# CTU.net
KiCad netlist of a schematic drawn in EAGLE
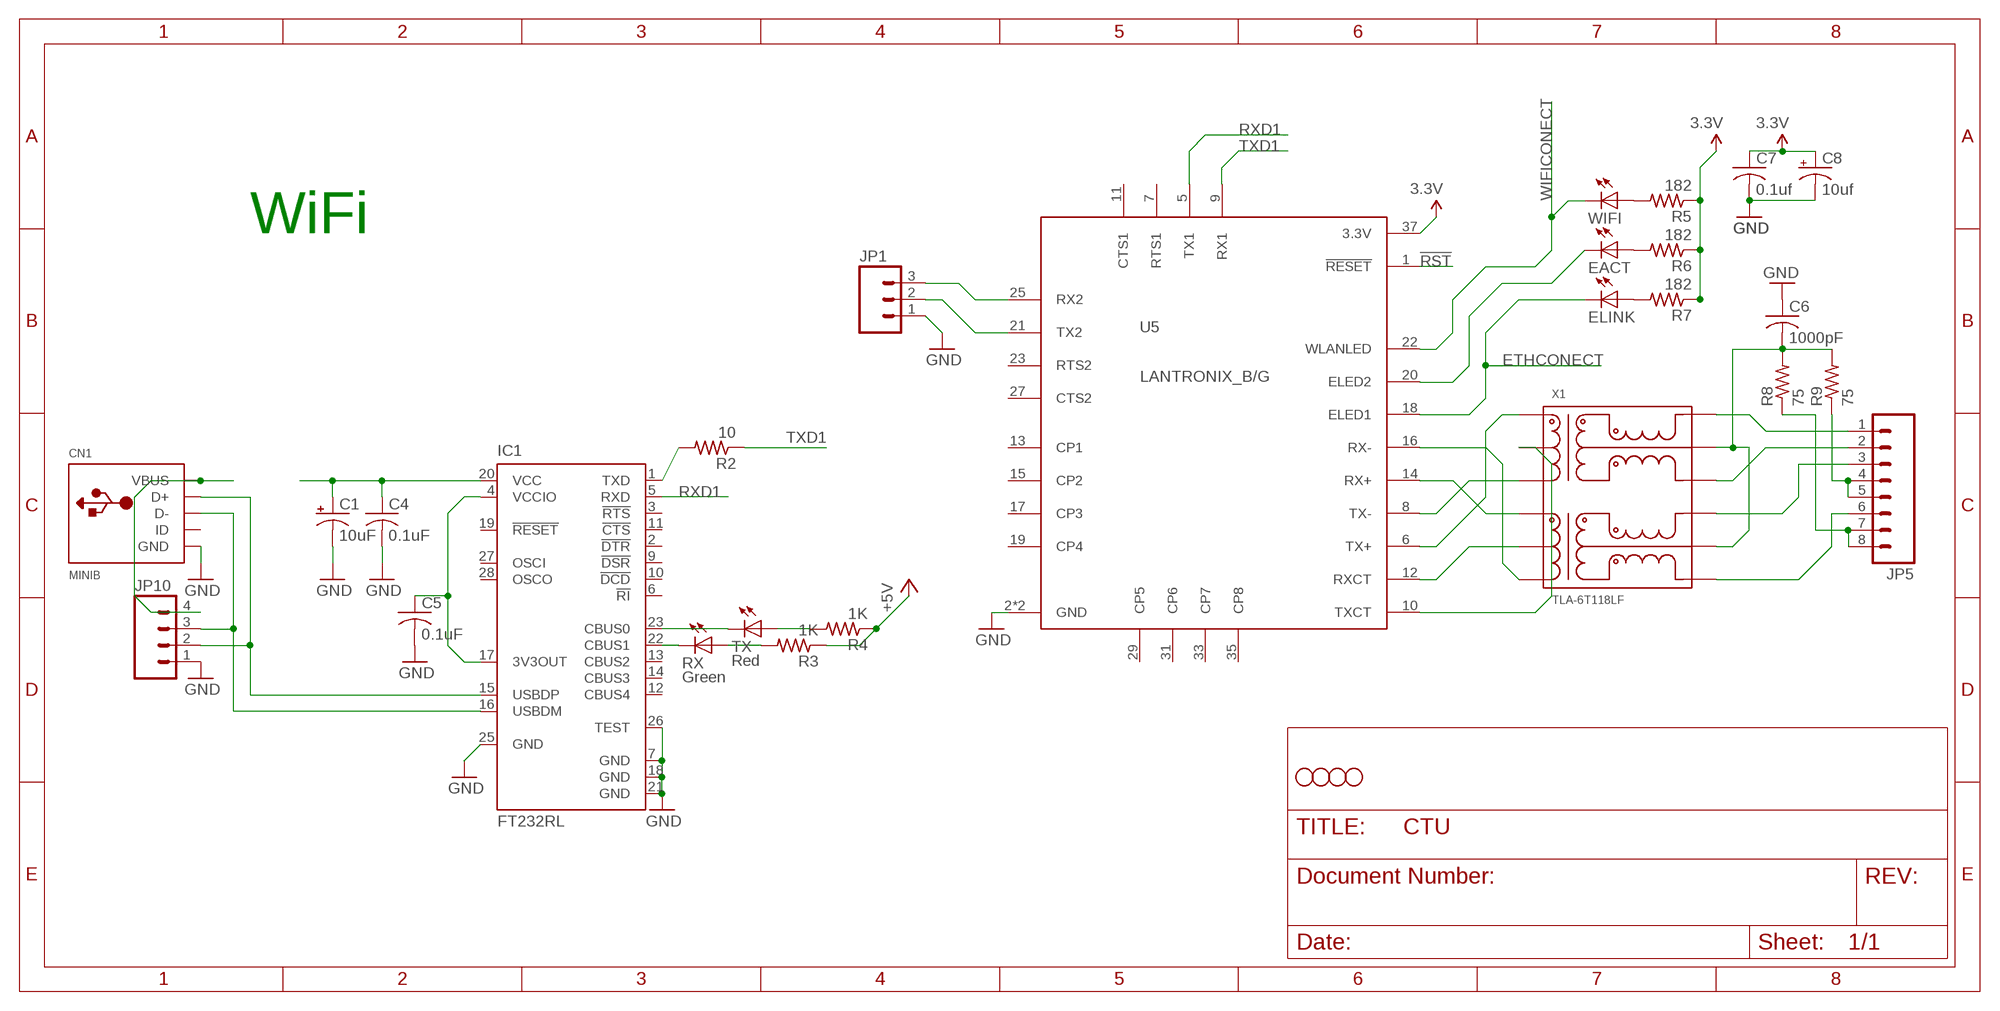
[diagram p0: schematic, sheet 1]

(export (version "E")
  (design (tool "Eeschema 10.0.6"))
  (components
    (comp (ref "C1")
      (value "10uF")
      (footprint "eagle-import:EIA3528-KIT")
      (libsource (lib "eagle-import") (part "CAP_POL3528-KIT"))
    )
    (comp (ref "C4")
      (value "0.1uF")
      (footprint "eagle-import:C0805K")
      (libsource (lib "eagle-import") (part "C-USC0805K"))
    )
    (comp (ref "C5")
      (value "0.1uF")
      (footprint "eagle-import:C0805K")
      (libsource (lib "eagle-import") (part "C-USC0805K"))
    )
    (comp (ref "C6")
      (value "1000pF")
      (footprint "eagle-import:C1812")
      (libsource (lib "eagle-import") (part "C-USC1812"))
    )
    (comp (ref "C7")
      (value "0.1uf")
      (footprint "eagle-import:C0805K")
      (libsource (lib "eagle-import") (part "C-USC0805K"))
    )
    (comp (ref "C8")
      (value "10uf")
      (footprint "eagle-import:EIA3528")
      (libsource (lib "eagle-import") (part "CAP_POL3528"))
    )
    (comp (ref "CN1")
      (value "MINIB")
      (footprint "eagle-import:USB-MINIB")
      (libsource (lib "eagle-import") (part "USBMINIB"))
    )
    (comp (ref "EACT")
      (value "LEDCHIP-LED0805")
      (footprint "eagle-import:CHIP-LED0805")
      (libsource (lib "eagle-import") (part "LEDCHIP-LED0805"))
    )
    (comp (ref "ELINK")
      (value "LEDCHIP-LED0805")
      (footprint "eagle-import:CHIP-LED0805")
      (libsource (lib "eagle-import") (part "LEDCHIP-LED0805"))
    )
    (comp (ref "IC1")
      (value "FT232RL")
      (footprint "eagle-import:SSOP28")
      (libsource (lib "eagle-import") (part "FT232RL"))
    )
    (comp (ref "JP1")
      (value "M03POLAR")
      (footprint "eagle-import:MOLEX-1X3")
      (libsource (lib "eagle-import") (part "M03POLAR"))
    )
    (comp (ref "JP2")
      (value "STAND-OFF")
      (footprint "eagle-import:STAND-OFF")
      (libsource (lib "eagle-import") (part "STAND-OFF"))
    )
    (comp (ref "JP3")
      (value "STAND-OFF")
      (footprint "eagle-import:STAND-OFF")
      (libsource (lib "eagle-import") (part "STAND-OFF"))
    )
    (comp (ref "JP4")
      (value "STAND-OFF")
      (footprint "eagle-import:STAND-OFF")
      (libsource (lib "eagle-import") (part "STAND-OFF"))
    )
    (comp (ref "JP5")
      (value "M08LOCK_LONGPADS")
      (footprint "eagle-import:1X08_LOCK_LONGPADS")
      (libsource (lib "eagle-import") (part "M08LOCK_LONGPADS"))
    )
    (comp (ref "JP6")
      (value "STAND-OFF")
      (footprint "eagle-import:STAND-OFF")
      (libsource (lib "eagle-import") (part "STAND-OFF"))
    )
    (comp (ref "JP10")
      (value "M04POLAR")
      (footprint "eagle-import:MOLEX-1X4")
      (libsource (lib "eagle-import") (part "M04POLAR"))
    )
    (comp (ref "R2")
      (value "10")
      (footprint "eagle-import:R0805")
      (libsource (lib "eagle-import") (part "R-US_R0805"))
    )
    (comp (ref "R3")
      (value "1K")
      (footprint "eagle-import:R0805")
      (libsource (lib "eagle-import") (part "R-US_R0805"))
    )
    (comp (ref "R4")
      (value "1K")
      (footprint "eagle-import:R0805")
      (libsource (lib "eagle-import") (part "R-US_R0805"))
    )
    (comp (ref "R5")
      (value "182")
      (footprint "eagle-import:R0805")
      (libsource (lib "eagle-import") (part "R-US_R0805"))
    )
    (comp (ref "R6")
      (value "182")
      (footprint "eagle-import:R0805")
      (libsource (lib "eagle-import") (part "R-US_R0805"))
    )
    (comp (ref "R7")
      (value "182")
      (footprint "eagle-import:R0805")
      (libsource (lib "eagle-import") (part "R-US_R0805"))
    )
    (comp (ref "R8")
      (value "75")
      (footprint "eagle-import:R0805")
      (libsource (lib "eagle-import") (part "R-US_R0805"))
    )
    (comp (ref "R9")
      (value "75")
      (footprint "eagle-import:R0805")
      (libsource (lib "eagle-import") (part "R-US_R0805"))
    )
    (comp (ref "RX")
      (value "Green")
      (footprint "eagle-import:CHIP-LED0805")
      (libsource (lib "eagle-import") (part "LEDCHIP-LED0805"))
    )
    (comp (ref "TX")
      (value "Red")
      (footprint "eagle-import:CHIP-LED0805")
      (libsource (lib "eagle-import") (part "LEDCHIP-LED0805"))
    )
    (comp (ref "U5")
      (value "LANTRONIX_B/G")
      (footprint "eagle-import:LANA_BTH")
      (libsource (lib "eagle-import") (part "LANTRONIX_A/B"))
    )
    (comp (ref "WIFI")
      (value "LEDCHIP-LED0805")
      (footprint "eagle-import:CHIP-LED0805")
      (libsource (lib "eagle-import") (part "LEDCHIP-LED0805"))
    )
    (comp (ref "X1")
      (value "TLA-6T118LF")
      (footprint "eagle-import:SO-16MOD")
      (libsource (lib "eagle-import") (part "TLA-6T118LF"))
    )
  )
  (nets
    (net (code "1") (name "+5V") (class "Default")
      (node (ref "R3") (pin "1") (pinfunction "1_1") (pintype "passive"))
      (node (ref "R4") (pin "1") (pinfunction "1_1") (pintype "passive"))
    )
    (net (code "2") (name "/ETHCONECT") (class "Default")
      (node (ref "ELINK") (pin "C") (pinfunction "C_C") (pintype "passive"))
      (node (ref "U5") (pin "18") (pinfunction "ELED1_18") (pintype "bidirectional"))
    )
    (net (code "3") (name "/RXD1") (class "Default")
      (node (ref "IC1") (pin "5") (pinfunction "RXD_5") (pintype "input"))
      (node (ref "U5") (pin "5") (pinfunction "TX1_5") (pintype "bidirectional"))
    )
    (net (code "4") (name "/TXD1") (class "Default")
      (node (ref "R2") (pin "1") (pinfunction "1_1") (pintype "passive"))
      (node (ref "U5") (pin "9") (pinfunction "RX1_9") (pintype "bidirectional"))
    )
    (net (code "5") (name "/WIFICONECT") (class "Default")
      (node (ref "U5") (pin "22") (pinfunction "WLANLED_22") (pintype "bidirectional"))
      (node (ref "WIFI") (pin "C") (pinfunction "C_C") (pintype "passive"))
    )
    (net (code "6") (name "/~{RST}") (class "Default")
      (node (ref "U5") (pin "1") (pinfunction "~{RESET}_1") (pintype "bidirectional"))
    )
    (net (code "7") (name "3.3V") (class "Default")
      (node (ref "C7") (pin "1") (pinfunction "1_1") (pintype "passive"))
      (node (ref "C8") (pin "A") (pinfunction "+_A") (pintype "passive"))
      (node (ref "R5") (pin "1") (pinfunction "1_1") (pintype "passive"))
      (node (ref "R6") (pin "1") (pinfunction "1_1") (pintype "passive"))
      (node (ref "R7") (pin "1") (pinfunction "1_1") (pintype "passive"))
      (node (ref "U5") (pin "37") (pinfunction "3.3V_37") (pintype "bidirectional"))
    )
    (net (code "8") (name "GND") (class "Default")
      (node (ref "C1") (pin "C") (pinfunction "-_C") (pintype "passive"))
      (node (ref "C4") (pin "2") (pinfunction "2_2") (pintype "passive"))
      (node (ref "C5") (pin "2") (pinfunction "2_2") (pintype "passive"))
      (node (ref "C6") (pin "1") (pinfunction "1_1") (pintype "passive"))
      (node (ref "C7") (pin "2") (pinfunction "2_2") (pintype "passive"))
      (node (ref "C8") (pin "C") (pinfunction "-_C") (pintype "passive"))
      (node (ref "CN1") (pin "GND") (pinfunction "GND_GND") (pintype "power_in"))
      (node (ref "IC1") (pin "18") (pinfunction "GND_18") (pintype "input"))
      (node (ref "IC1") (pin "21") (pinfunction "GND_21") (pintype "input"))
      (node (ref "IC1") (pin "25") (pinfunction "GND_25") (pintype "input"))
      (node (ref "IC1") (pin "26") (pinfunction "TEST_26") (pintype "input"))
      (node (ref "IC1") (pin "7") (pinfunction "GND_7") (pintype "input"))
      (node (ref "JP1") (pin "1") (pinfunction "1_1") (pintype "passive"))
      (node (ref "JP10") (pin "1") (pinfunction "1_1") (pintype "passive"))
      (node (ref "U5") (pin "2") (pinfunction "GND_2") (pintype "bidirectional"))
      (node (ref "U5") (pin "39") (pinfunction "GND_39") (pintype "bidirectional"))
    )
    (net (code "9") (name "Net-(C1-+)") (class "Default")
      (node (ref "C1") (pin "A") (pinfunction "+_A") (pintype "passive"))
      (node (ref "C4") (pin "1") (pinfunction "1_1") (pintype "passive"))
      (node (ref "IC1") (pin "20") (pinfunction "VCC_20") (pintype "input"))
    )
    (net (code "10") (name "Net-(C6-Pad2)") (class "Default")
      (node (ref "C6") (pin "2") (pinfunction "2_2") (pintype "passive"))
      (node (ref "R8") (pin "2") (pinfunction "2_2") (pintype "passive"))
      (node (ref "R9") (pin "2") (pinfunction "2_2") (pintype "passive"))
      (node (ref "X1") (pin "10") (pinfunction "10_10") (pintype "bidirectional"))
      (node (ref "X1") (pin "15") (pinfunction "15_15") (pintype "bidirectional"))
    )
    (net (code "11") (name "Net-(CN1-PadVBUS)") (class "Default")
      (node (ref "CN1") (pin "VBUS") (pinfunction "VBUS_VBUS") (pintype "power_in"))
      (node (ref "JP10") (pin "4") (pinfunction "4_4") (pintype "passive"))
    )
    (net (code "12") (name "Net-(EACT-PadA)") (class "Default")
      (node (ref "EACT") (pin "A") (pinfunction "A_A") (pintype "passive"))
      (node (ref "R6") (pin "2") (pinfunction "2_2") (pintype "passive"))
    )
    (net (code "13") (name "Net-(ELINK-PadA)") (class "Default")
      (node (ref "ELINK") (pin "A") (pinfunction "A_A") (pintype "passive"))
      (node (ref "R7") (pin "2") (pinfunction "2_2") (pintype "passive"))
    )
    (net (code "14") (name "Net-(IC1-3V3OUT)") (class "Default")
      (node (ref "C5") (pin "1") (pinfunction "1_1") (pintype "passive"))
      (node (ref "IC1") (pin "17") (pinfunction "3V3OUT_17") (pintype "input"))
      (node (ref "IC1") (pin "4") (pinfunction "VCCIO_4") (pintype "input"))
    )
    (net (code "15") (name "Net-(IC1-CBUS0)") (class "Default")
      (node (ref "IC1") (pin "23") (pinfunction "CBUS0_23") (pintype "input"))
      (node (ref "TX") (pin "C") (pinfunction "C_C") (pintype "passive"))
    )
    (net (code "16") (name "Net-(IC1-CBUS1)") (class "Default")
      (node (ref "IC1") (pin "22") (pinfunction "CBUS1_22") (pintype "input"))
      (node (ref "RX") (pin "C") (pinfunction "C_C") (pintype "passive"))
    )
    (net (code "17") (name "Net-(IC1-TXD)") (class "Default")
      (node (ref "IC1") (pin "1") (pinfunction "TXD_1") (pintype "input"))
      (node (ref "R2") (pin "2") (pinfunction "2_2") (pintype "passive"))
    )
    (net (code "18") (name "Net-(IC1-USBDM)") (class "Default")
      (node (ref "CN1") (pin "D-") (pinfunction "D-_D-") (pintype "bidirectional"))
      (node (ref "IC1") (pin "16") (pinfunction "USBDM_16") (pintype "input"))
      (node (ref "JP10") (pin "3") (pinfunction "3_3") (pintype "passive"))
    )
    (net (code "19") (name "Net-(IC1-USBDP)") (class "Default")
      (node (ref "CN1") (pin "D+") (pinfunction "D+_D+") (pintype "bidirectional"))
      (node (ref "IC1") (pin "15") (pinfunction "USBDP_15") (pintype "input"))
      (node (ref "JP10") (pin "2") (pinfunction "2_2") (pintype "passive"))
    )
    (net (code "20") (name "Net-(JP5-Pad1)") (class "Default")
      (node (ref "JP5") (pin "1") (pinfunction "1_1") (pintype "passive"))
      (node (ref "X1") (pin "16") (pinfunction "16_16") (pintype "bidirectional"))
    )
    (net (code "21") (name "Net-(JP5-Pad2)") (class "Default")
      (node (ref "JP5") (pin "2") (pinfunction "2_2") (pintype "passive"))
      (node (ref "X1") (pin "14") (pinfunction "14_14") (pintype "bidirectional"))
    )
    (net (code "22") (name "Net-(JP5-Pad3)") (class "Default")
      (node (ref "JP5") (pin "3") (pinfunction "3_3") (pintype "passive"))
      (node (ref "X1") (pin "11") (pinfunction "11_11") (pintype "bidirectional"))
    )
    (net (code "23") (name "Net-(JP5-Pad4)") (class "Default")
      (node (ref "JP5") (pin "4") (pinfunction "4_4") (pintype "passive"))
      (node (ref "JP5") (pin "5") (pinfunction "5_5") (pintype "passive"))
      (node (ref "R9") (pin "1") (pinfunction "1_1") (pintype "passive"))
    )
    (net (code "24") (name "Net-(JP5-Pad6)") (class "Default")
      (node (ref "JP5") (pin "6") (pinfunction "6_6") (pintype "passive"))
      (node (ref "X1") (pin "9") (pinfunction "9_9") (pintype "bidirectional"))
    )
    (net (code "25") (name "Net-(JP5-Pad7)") (class "Default")
      (node (ref "JP5") (pin "7") (pinfunction "7_7") (pintype "passive"))
      (node (ref "JP5") (pin "8") (pinfunction "8_8") (pintype "passive"))
      (node (ref "R8") (pin "1") (pinfunction "1_1") (pintype "passive"))
    )
    (net (code "26") (name "Net-(R3-Pad2)") (class "Default")
      (node (ref "R3") (pin "2") (pinfunction "2_2") (pintype "passive"))
      (node (ref "RX") (pin "A") (pinfunction "A_A") (pintype "passive"))
    )
    (net (code "27") (name "Net-(R4-Pad2)") (class "Default")
      (node (ref "R4") (pin "2") (pinfunction "2_2") (pintype "passive"))
      (node (ref "TX") (pin "A") (pinfunction "A_A") (pintype "passive"))
    )
    (net (code "28") (name "Net-(R5-Pad2)") (class "Default")
      (node (ref "R5") (pin "2") (pinfunction "2_2") (pintype "passive"))
      (node (ref "WIFI") (pin "A") (pinfunction "A_A") (pintype "passive"))
    )
    (net (code "29") (name "Net-(U5-ELED2)") (class "Default")
      (node (ref "EACT") (pin "C") (pinfunction "C_C") (pintype "passive"))
      (node (ref "U5") (pin "20") (pinfunction "ELED2_20") (pintype "bidirectional"))
    )
    (net (code "30") (name "Net-(U5-RX+)") (class "Default")
      (node (ref "U5") (pin "14") (pinfunction "RX+_14") (pintype "bidirectional"))
      (node (ref "X1") (pin "6") (pinfunction "6_6") (pintype "bidirectional"))
    )
    (net (code "31") (name "Net-(U5-RX-)") (class "Default")
      (node (ref "U5") (pin "16") (pinfunction "RX-_16") (pintype "bidirectional"))
      (node (ref "X1") (pin "8") (pinfunction "8_8") (pintype "bidirectional"))
    )
    (net (code "32") (name "Net-(U5-RX2)") (class "Default")
      (node (ref "JP1") (pin "3") (pinfunction "3_3") (pintype "passive"))
      (node (ref "U5") (pin "25") (pinfunction "RX2_25") (pintype "bidirectional"))
    )
    (net (code "33") (name "Net-(U5-RXCT)") (class "Default")
      (node (ref "U5") (pin "12") (pinfunction "RXCT_12") (pintype "bidirectional"))
      (node (ref "X1") (pin "7") (pinfunction "7_7") (pintype "bidirectional"))
    )
    (net (code "34") (name "Net-(U5-TX+)") (class "Default")
      (node (ref "U5") (pin "6") (pinfunction "TX+_6") (pintype "bidirectional"))
      (node (ref "X1") (pin "1") (pinfunction "1_1") (pintype "bidirectional"))
    )
    (net (code "35") (name "Net-(U5-TX-)") (class "Default")
      (node (ref "U5") (pin "8") (pinfunction "TX-_8") (pintype "bidirectional"))
      (node (ref "X1") (pin "3") (pinfunction "3_3") (pintype "bidirectional"))
    )
    (net (code "36") (name "Net-(U5-TX2)") (class "Default")
      (node (ref "JP1") (pin "2") (pinfunction "2_2") (pintype "passive"))
      (node (ref "U5") (pin "21") (pinfunction "TX2_21") (pintype "bidirectional"))
    )
    (net (code "37") (name "Net-(U5-TXCT)") (class "Default")
      (node (ref "U5") (pin "10") (pinfunction "TXCT_10") (pintype "bidirectional"))
      (node (ref "X1") (pin "2") (pinfunction "2_2") (pintype "bidirectional"))
    )
    (net (code "38") (name "unconnected-(CN1-PadID)") (class "Default")
      (node (ref "CN1") (pin "ID") (pinfunction "ID_ID") (pintype "bidirectional"))
    )
    (net (code "39") (name "unconnected-(IC1-CBUS2-Pad13)") (class "Default")
      (node (ref "IC1") (pin "13") (pinfunction "CBUS2_13") (pintype "input"))
    )
    (net (code "40") (name "unconnected-(IC1-CBUS3-Pad14)") (class "Default")
      (node (ref "IC1") (pin "14") (pinfunction "CBUS3_14") (pintype "input"))
    )
    (net (code "41") (name "unconnected-(IC1-CBUS4-Pad12)") (class "Default")
      (node (ref "IC1") (pin "12") (pinfunction "CBUS4_12") (pintype "input"))
    )
    (net (code "42") (name "unconnected-(IC1-OSCI-Pad27)") (class "Default")
      (node (ref "IC1") (pin "27") (pinfunction "OSCI_27") (pintype "input"))
    )
    (net (code "43") (name "unconnected-(IC1-OSCO-Pad28)") (class "Default")
      (node (ref "IC1") (pin "28") (pinfunction "OSCO_28") (pintype "input"))
    )
    (net (code "44") (name "unconnected-(IC1-~{CTS}-Pad11)") (class "Default")
      (node (ref "IC1") (pin "11") (pinfunction "~{CTS}_11") (pintype "input"))
    )
    (net (code "45") (name "unconnected-(IC1-~{DCD}-Pad10)") (class "Default")
      (node (ref "IC1") (pin "10") (pinfunction "~{DCD}_10") (pintype "input"))
    )
    (net (code "46") (name "unconnected-(IC1-~{DSR}-Pad9)") (class "Default")
      (node (ref "IC1") (pin "9") (pinfunction "~{DSR}_9") (pintype "input"))
    )
    (net (code "47") (name "unconnected-(IC1-~{DTR}-Pad2)") (class "Default")
      (node (ref "IC1") (pin "2") (pinfunction "~{DTR}_2") (pintype "input"))
    )
    (net (code "48") (name "unconnected-(IC1-~{RESET}-Pad19)") (class "Default")
      (node (ref "IC1") (pin "19") (pinfunction "~{RESET}_19") (pintype "input"))
    )
    (net (code "49") (name "unconnected-(IC1-~{RI}-Pad6)") (class "Default")
      (node (ref "IC1") (pin "6") (pinfunction "~{RI}_6") (pintype "input"))
    )
    (net (code "50") (name "unconnected-(IC1-~{RTS}-Pad3)") (class "Default")
      (node (ref "IC1") (pin "3") (pinfunction "~{RTS}_3") (pintype "input"))
    )
    (net (code "51") (name "unconnected-(U5-CP1-Pad13)") (class "Default")
      (node (ref "U5") (pin "13") (pinfunction "CP1_13") (pintype "bidirectional"))
    )
    (net (code "52") (name "unconnected-(U5-CP2-Pad15)") (class "Default")
      (node (ref "U5") (pin "15") (pinfunction "CP2_15") (pintype "bidirectional"))
    )
    (net (code "53") (name "unconnected-(U5-CP3-Pad17)") (class "Default")
      (node (ref "U5") (pin "17") (pinfunction "CP3_17") (pintype "bidirectional"))
    )
    (net (code "54") (name "unconnected-(U5-CP4-Pad19)") (class "Default")
      (node (ref "U5") (pin "19") (pinfunction "CP4_19") (pintype "bidirectional"))
    )
    (net (code "55") (name "unconnected-(U5-CP5-Pad29)") (class "Default")
      (node (ref "U5") (pin "29") (pinfunction "CP5_29") (pintype "bidirectional"))
    )
    (net (code "56") (name "unconnected-(U5-CP6-Pad31)") (class "Default")
      (node (ref "U5") (pin "31") (pinfunction "CP6_31") (pintype "bidirectional"))
    )
    (net (code "57") (name "unconnected-(U5-CP7-Pad33)") (class "Default")
      (node (ref "U5") (pin "33") (pinfunction "CP7_33") (pintype "bidirectional"))
    )
    (net (code "58") (name "unconnected-(U5-CP8-Pad35)") (class "Default")
      (node (ref "U5") (pin "35") (pinfunction "CP8_35") (pintype "bidirectional"))
    )
    (net (code "59") (name "unconnected-(U5-CTS1-Pad11)") (class "Default")
      (node (ref "U5") (pin "11") (pinfunction "CTS1_11") (pintype "bidirectional"))
    )
    (net (code "60") (name "unconnected-(U5-CTS2-Pad27)") (class "Default")
      (node (ref "U5") (pin "27") (pinfunction "CTS2_27") (pintype "bidirectional"))
    )
    (net (code "61") (name "unconnected-(U5-RTS1-Pad7)") (class "Default")
      (node (ref "U5") (pin "7") (pinfunction "RTS1_7") (pintype "bidirectional"))
    )
    (net (code "62") (name "unconnected-(U5-RTS2-Pad23)") (class "Default")
      (node (ref "U5") (pin "23") (pinfunction "RTS2_23") (pintype "bidirectional"))
    )
  )
)
